# TPL-transformer.net
KiCad netlist of a schematic drawn in Altium Designer
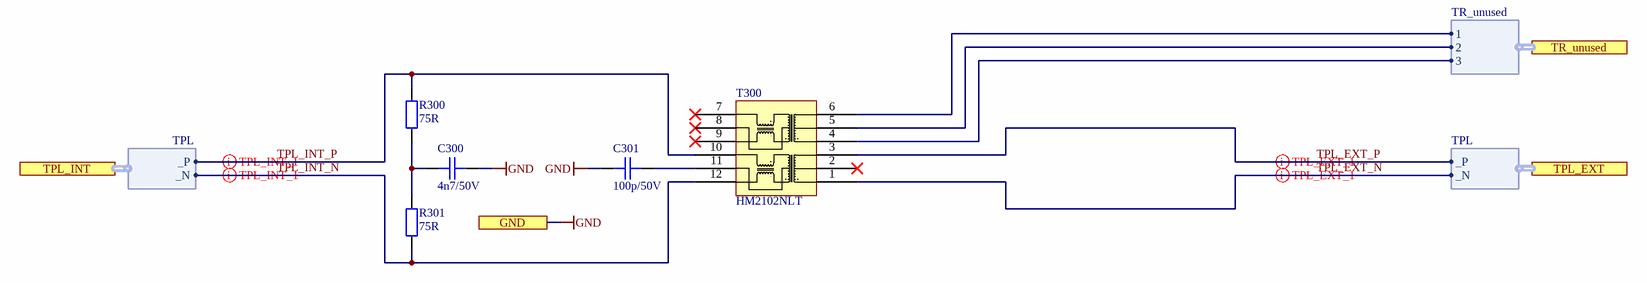
[diagram p0: TPL-transformer.SchDoc]

(export (version "E")
  (design (tool "Eeschema 10.0.6"))
  (components
    (comp (ref "C300")
      (value "4n7/50V")
      (footprint "CAPC1608X08N")
      (description "MLCC")
      (fields (field (name "PART NUMBER") "gen_C_ceramic_4n7_50V_X7R_0603"))
      (libsource (lib "OE750") (part "C"))
    )
    (comp (ref "C301")
      (value "100p/50V")
      (footprint "CAPC1608X08N")
      (description "MLCC")
      (fields
        (field (name "PART NUMBER") "gen_C_ceramic_100p_50V_C0G_0603")
        (field (name "TOLERANCE") "± 10%")
      )
      (libsource (lib "OE750") (part "C"))
    )
    (comp (ref "R300")
      (value "75R")
      (footprint "RESC1608X05N")
      (description "SMD Resistor 75R 0603")
      (fields (field (name "PART NUMBER") "gen_R_75R_0603") (field (name "TOLERANCE") "1%"))
      (libsource (lib "OE750") (part "R"))
    )
    (comp (ref "R301")
      (value "75R")
      (footprint "RESC1608X05N")
      (description "SMD Resistor 75R 0603")
      (fields (field (name "PART NUMBER") "gen_R_75R_0603") (field (name "TOLERANCE") "1%"))
      (libsource (lib "OE750") (part "R"))
    )
    (comp (ref "T300")
      (value "HM2102NLT")
      (footprint "HM2102NL")
      (description "Pulse HM2102NLT BMS Transformer")
      (fields (field (name "MANUFACTURER") "Pulse"))
      (libsource (lib "OE750") (part "HM2102NL"))
    )
  )
  (nets
    (net (code "3") (name "/1") (class "Default") (node (ref "T300") (pin "6") (pintype "passive")))
    (net (code "4") (name "/2") (class "Default") (node (ref "T300") (pin "5") (pintype "passive")))
    (net (code "5") (name "/3") (class "Default") (node (ref "T300") (pin "4") (pintype "passive")))
    (net (code "6") (name "/TPL_EXT_N") (class "Default") (node (ref "T300") (pin "1") (pintype "passive")))
    (net (code "7") (name "/TPL_EXT_P") (class "Default") (node (ref "T300") (pin "3") (pintype "passive")))
    (net (code "8") (name "/TPL_INT_N") (class "Default")
      (node (ref "R301") (pin "1") (pinfunction "1_1") (pintype "passive"))
      (node (ref "T300") (pin "12") (pintype "passive"))
    )
    (net (code "9") (name "/TPL_INT_P") (class "Default")
      (node (ref "R300") (pin "2") (pinfunction "2_2") (pintype "passive"))
      (node (ref "T300") (pin "10") (pintype "passive"))
    )
    (net (code "12") (name "GND") (class "Default")
      (node (ref "C300") (pin "2") (pinfunction "2_2") (pintype "passive"))
      (node (ref "C301") (pin "1") (pinfunction "1_1") (pintype "passive"))
    )
    (net (code "13") (name "Net-(C300-Pad1)") (class "Default")
      (node (ref "C300") (pin "1") (pinfunction "1_1") (pintype "passive"))
      (node (ref "R300") (pin "1") (pinfunction "1_1") (pintype "passive"))
      (node (ref "R301") (pin "2") (pinfunction "2_2") (pintype "passive"))
    )
    (net (code "14") (name "Net-(C301-Pad2)") (class "Default")
      (node (ref "C301") (pin "2") (pinfunction "2_2") (pintype "passive"))
      (node (ref "T300") (pin "11") (pintype "passive"))
    )
    (net (code "15") (name "unconnected-(T300-Pad2)") (class "Default")
      (node (ref "T300") (pin "2") (pintype "passive+no_connect"))
    )
    (net (code "16") (name "unconnected-(T300-Pad7)") (class "Default")
      (node (ref "T300") (pin "7") (pintype "passive+no_connect"))
    )
    (net (code "17") (name "unconnected-(T300-Pad8)") (class "Default")
      (node (ref "T300") (pin "8") (pintype "passive+no_connect"))
    )
    (net (code "18") (name "unconnected-(T300-Pad9)") (class "Default")
      (node (ref "T300") (pin "9") (pintype "passive+no_connect"))
    )
  )
)
